# SCH_Task7_3D_PCB_Design_2022-05-29.net
KiCad netlist of a schematic drawn in EasyEDA
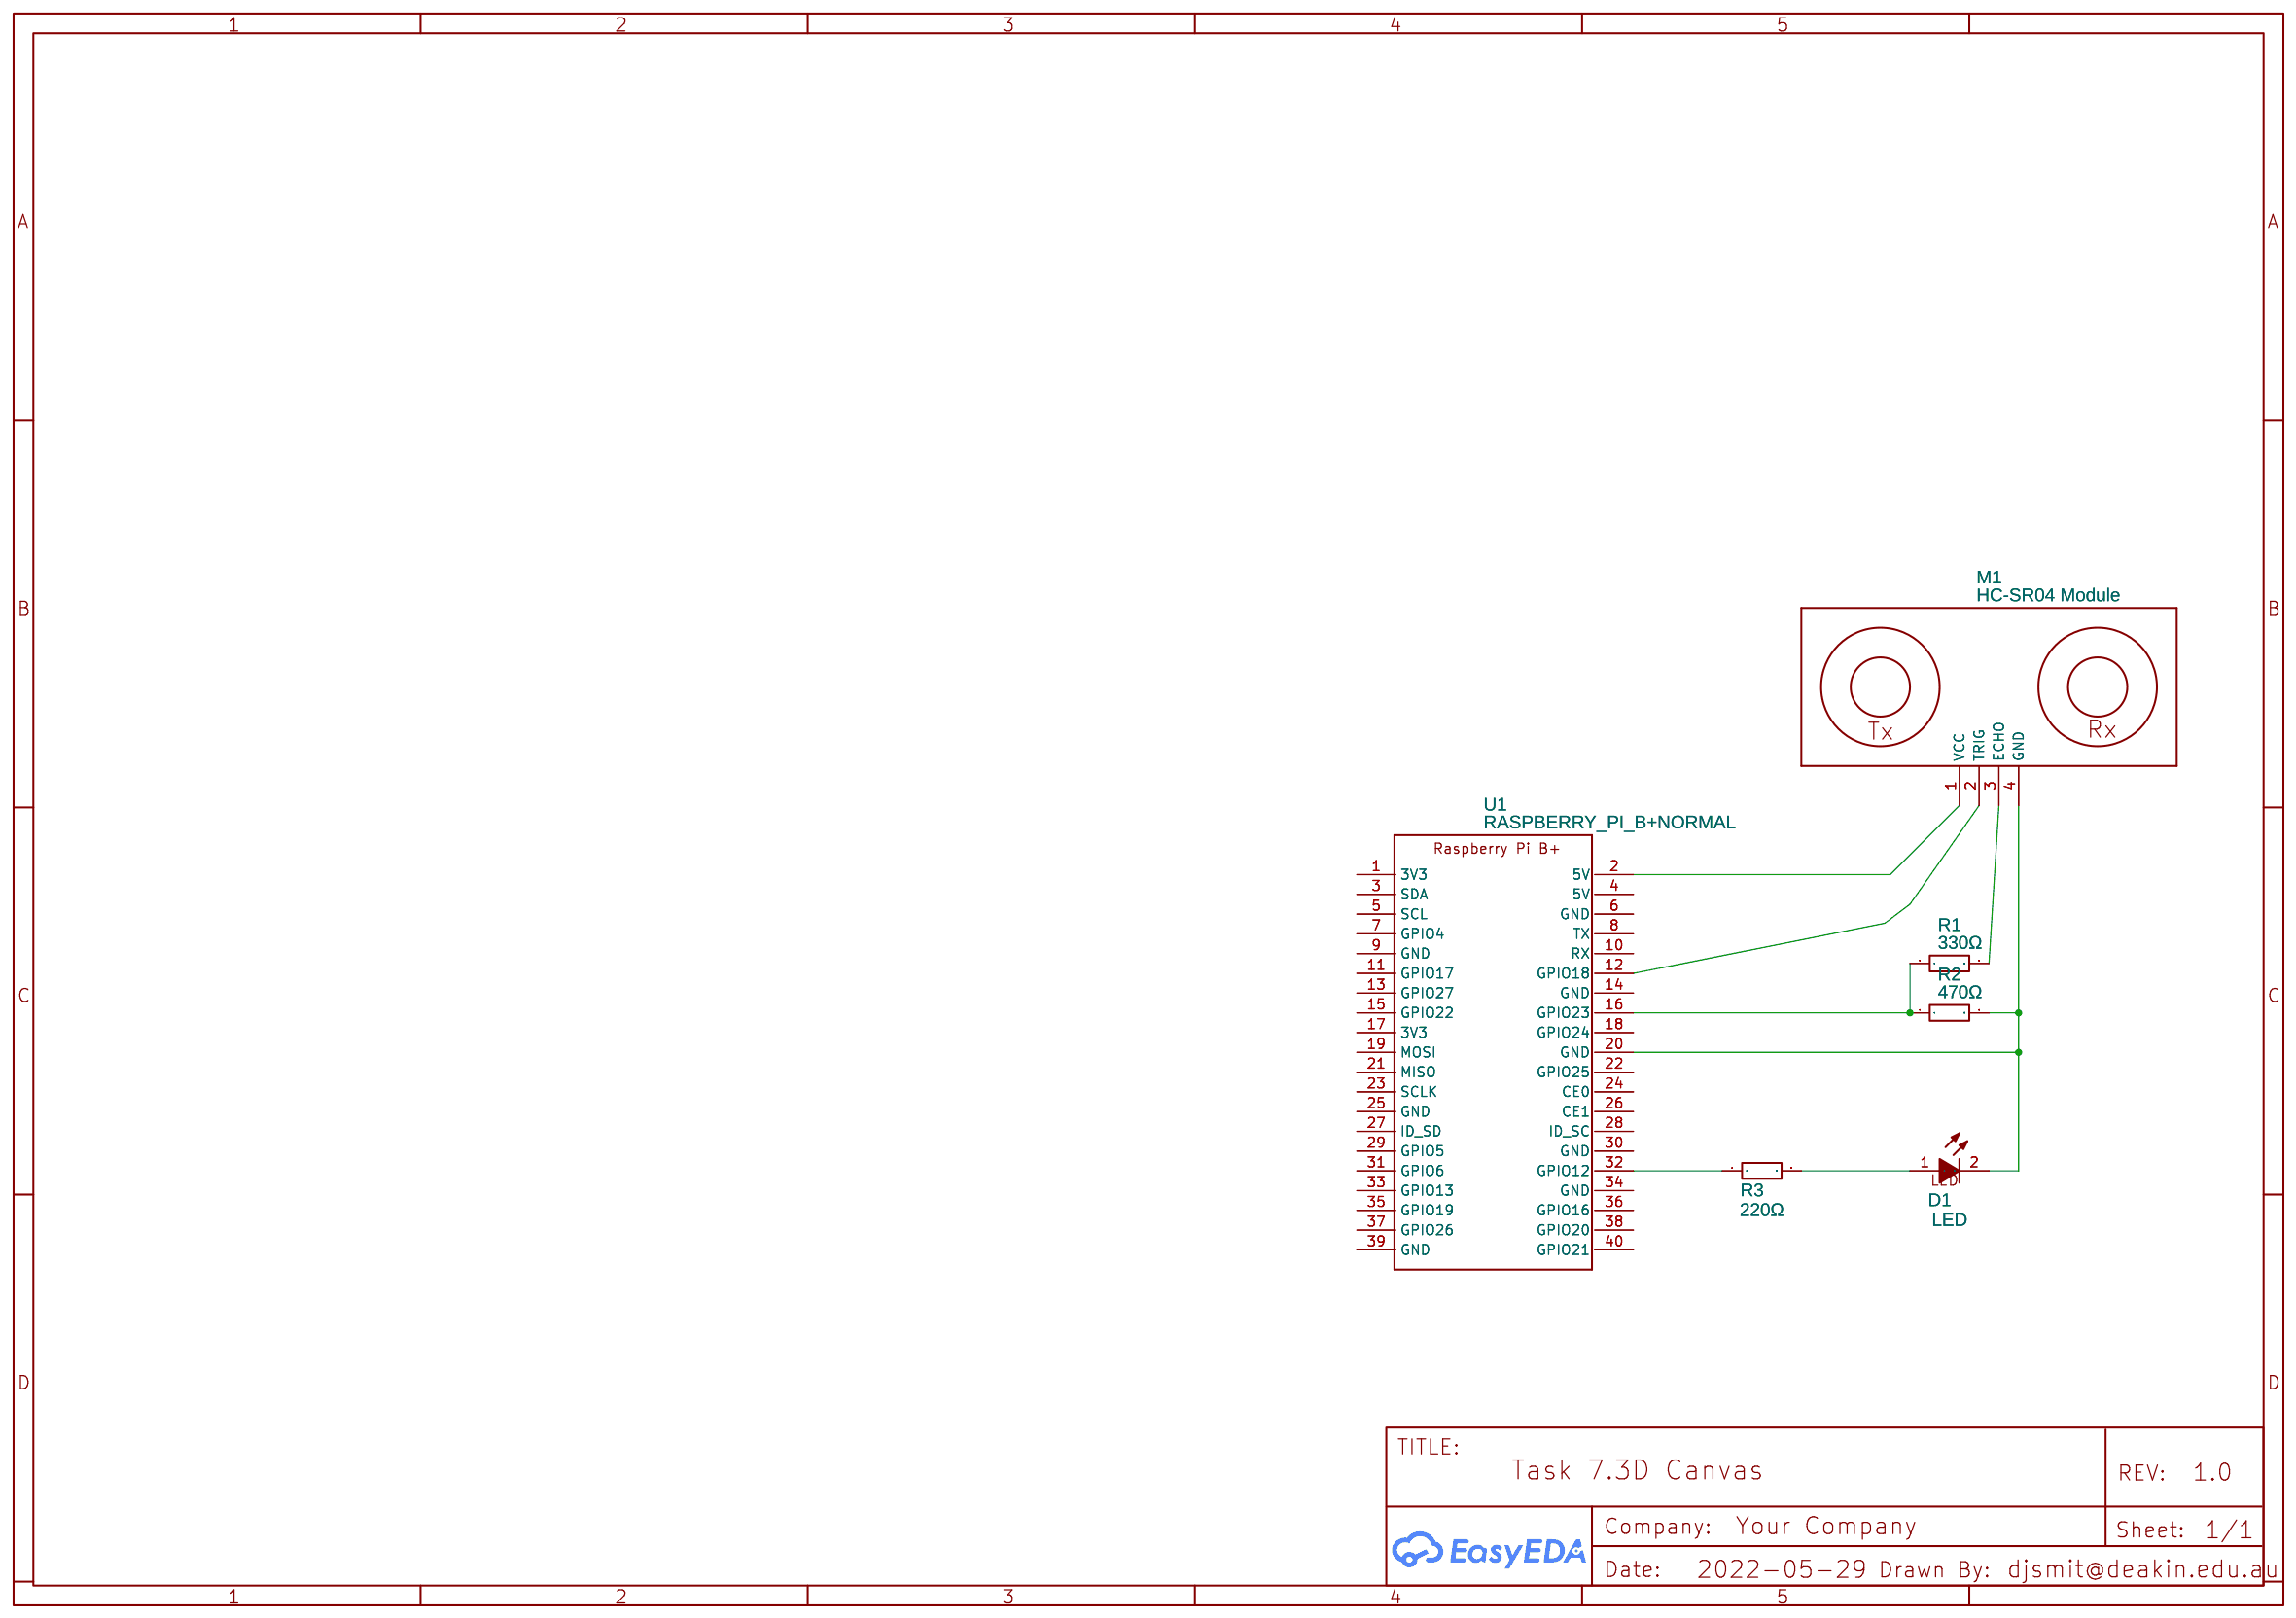
[diagram p0: schematic sheet]

(export (version "E")
  (design (tool "Eeschema 10.0.6"))
  (components
    (comp (ref "D1")
      (value "LED")
      (fields (field (name "BOM_Manufacturer Part") "5600") (field (name "BOM_Supplier Part") "L20325-ND"))
      (libsource (lib "") (part "LED"))
    )
    (comp (ref "M1") (value "HC-SR04 Module") (libsource (lib "") (part "HC-SR04 Module")))
    (comp (ref "R1")
      (value "330Ω")
      (fields
        (field (name "BOM_Manufacturer Part") "MFR0W4F3300A50")
        (field (name "BOM_Supplier Part") "C58608")
      )
      (libsource (lib "") (part "330 OHM Resistor THT (c58608)"))
    )
    (comp (ref "R2")
      (value "470Ω")
      (fields
        (field (name "BOM_Manufacturer Part") "MFR0W4F3300A50")
        (field (name "BOM_Supplier Part") "C58608")
      )
      (libsource (lib "") (part "330 OHM Resistor THT (c58608)"))
    )
    (comp (ref "R3")
      (value "220Ω")
      (fields
        (field (name "BOM_Manufacturer Part") "MFR0W4F3300A50")
        (field (name "BOM_Supplier Part") "C58608")
      )
      (libsource (lib "") (part "330 OHM Resistor THT (c58608)"))
    )
    (comp (ref "U1") (value "RASPBERRY_PI_B+NORMAL") (libsource (lib "") (part "RASPBERRY_PI_B+NORMAL")))
  )
  (nets
    (net (code "1") (name "Net-(D1-A)") (class "Default")
      (node (ref "D1") (pin "1") (pinfunction "A_1") (pintype "input"))
      (node (ref "R3") (pin "2") (pinfunction "2_2") (pintype "input"))
    )
    (net (code "2") (name "Net-(D1-K)") (class "Default")
      (node (ref "D1") (pin "2") (pinfunction "K_2") (pintype "input"))
      (node (ref "M1") (pin "4") (pinfunction "GND_4") (pintype "passive"))
      (node (ref "R2") (pin "2") (pinfunction "2_2") (pintype "input"))
      (node (ref "U1") (pin "20") (pinfunction "GND_20") (pintype "bidirectional"))
    )
    (net (code "3") (name "Net-(M1-ECHO)") (class "Default")
      (node (ref "M1") (pin "3") (pinfunction "ECHO_3") (pintype "output"))
      (node (ref "R1") (pin "2") (pinfunction "2_2") (pintype "input"))
    )
    (net (code "4") (name "Net-(M1-TRIG)") (class "Default")
      (node (ref "M1") (pin "2") (pinfunction "TRIG_2") (pintype "input"))
      (node (ref "U1") (pin "12") (pinfunction "GPIO18_12") (pintype "bidirectional"))
    )
    (net (code "5") (name "Net-(M1-VCC)") (class "Default")
      (node (ref "M1") (pin "1") (pinfunction "VCC_1") (pintype "passive"))
      (node (ref "U1") (pin "2") (pinfunction "5V_2") (pintype "bidirectional"))
    )
    (net (code "6") (name "Net-(U1-GPIO12)") (class "Default")
      (node (ref "R3") (pin "1") (pinfunction "1_1") (pintype "input"))
      (node (ref "U1") (pin "32") (pinfunction "GPIO12_32") (pintype "bidirectional"))
    )
    (net (code "7") (name "Net-(U1-GPIO23)") (class "Default")
      (node (ref "R1") (pin "1") (pinfunction "1_1") (pintype "input"))
      (node (ref "R2") (pin "1") (pinfunction "1_1") (pintype "input"))
      (node (ref "U1") (pin "16") (pinfunction "GPIO23_16") (pintype "bidirectional"))
    )
    (net (code "8") (name "unconnected-(U1-3V3-Pad1)") (class "Default")
      (node (ref "U1") (pin "1") (pinfunction "3V3_1") (pintype "bidirectional"))
    )
    (net (code "9") (name "unconnected-(U1-3V3-Pad17)") (class "Default")
      (node (ref "U1") (pin "17") (pinfunction "3V3_17") (pintype "bidirectional"))
    )
    (net (code "10") (name "unconnected-(U1-5V-Pad4)") (class "Default")
      (node (ref "U1") (pin "4") (pinfunction "5V_4") (pintype "bidirectional"))
    )
    (net (code "11") (name "unconnected-(U1-CE0-Pad24)") (class "Default")
      (node (ref "U1") (pin "24") (pinfunction "CE0_24") (pintype "bidirectional"))
    )
    (net (code "12") (name "unconnected-(U1-CE1-Pad26)") (class "Default")
      (node (ref "U1") (pin "26") (pinfunction "CE1_26") (pintype "bidirectional"))
    )
    (net (code "13") (name "unconnected-(U1-GND-Pad6)") (class "Default")
      (node (ref "U1") (pin "6") (pinfunction "GND_6") (pintype "bidirectional"))
    )
    (net (code "14") (name "unconnected-(U1-GND-Pad9)") (class "Default")
      (node (ref "U1") (pin "9") (pinfunction "GND_9") (pintype "bidirectional"))
    )
    (net (code "15") (name "unconnected-(U1-GND-Pad14)") (class "Default")
      (node (ref "U1") (pin "14") (pinfunction "GND_14") (pintype "bidirectional"))
    )
    (net (code "16") (name "unconnected-(U1-GND-Pad25)") (class "Default")
      (node (ref "U1") (pin "25") (pinfunction "GND_25") (pintype "bidirectional"))
    )
    (net (code "17") (name "unconnected-(U1-GND-Pad30)") (class "Default")
      (node (ref "U1") (pin "30") (pinfunction "GND_30") (pintype "bidirectional"))
    )
    (net (code "18") (name "unconnected-(U1-GND-Pad34)") (class "Default")
      (node (ref "U1") (pin "34") (pinfunction "GND_34") (pintype "bidirectional"))
    )
    (net (code "19") (name "unconnected-(U1-GND-Pad39)") (class "Default")
      (node (ref "U1") (pin "39") (pinfunction "GND_39") (pintype "bidirectional"))
    )
    (net (code "20") (name "unconnected-(U1-GPIO4-Pad7)") (class "Default")
      (node (ref "U1") (pin "7") (pinfunction "GPIO4_7") (pintype "bidirectional"))
    )
    (net (code "21") (name "unconnected-(U1-GPIO5-Pad29)") (class "Default")
      (node (ref "U1") (pin "29") (pinfunction "GPIO5_29") (pintype "bidirectional"))
    )
    (net (code "22") (name "unconnected-(U1-GPIO6-Pad31)") (class "Default")
      (node (ref "U1") (pin "31") (pinfunction "GPIO6_31") (pintype "bidirectional"))
    )
    (net (code "23") (name "unconnected-(U1-GPIO13-Pad33)") (class "Default")
      (node (ref "U1") (pin "33") (pinfunction "GPIO13_33") (pintype "bidirectional"))
    )
    (net (code "24") (name "unconnected-(U1-GPIO16-Pad36)") (class "Default")
      (node (ref "U1") (pin "36") (pinfunction "GPIO16_36") (pintype "bidirectional"))
    )
    (net (code "25") (name "unconnected-(U1-GPIO17-Pad11)") (class "Default")
      (node (ref "U1") (pin "11") (pinfunction "GPIO17_11") (pintype "bidirectional"))
    )
    (net (code "26") (name "unconnected-(U1-GPIO19-Pad35)") (class "Default")
      (node (ref "U1") (pin "35") (pinfunction "GPIO19_35") (pintype "bidirectional"))
    )
    (net (code "27") (name "unconnected-(U1-GPIO20-Pad38)") (class "Default")
      (node (ref "U1") (pin "38") (pinfunction "GPIO20_38") (pintype "bidirectional"))
    )
    (net (code "28") (name "unconnected-(U1-GPIO21-Pad40)") (class "Default")
      (node (ref "U1") (pin "40") (pinfunction "GPIO21_40") (pintype "bidirectional"))
    )
    (net (code "29") (name "unconnected-(U1-GPIO22-Pad15)") (class "Default")
      (node (ref "U1") (pin "15") (pinfunction "GPIO22_15") (pintype "bidirectional"))
    )
    (net (code "30") (name "unconnected-(U1-GPIO24-Pad18)") (class "Default")
      (node (ref "U1") (pin "18") (pinfunction "GPIO24_18") (pintype "bidirectional"))
    )
    (net (code "31") (name "unconnected-(U1-GPIO25-Pad22)") (class "Default")
      (node (ref "U1") (pin "22") (pinfunction "GPIO25_22") (pintype "bidirectional"))
    )
    (net (code "32") (name "unconnected-(U1-GPIO26-Pad37)") (class "Default")
      (node (ref "U1") (pin "37") (pinfunction "GPIO26_37") (pintype "bidirectional"))
    )
    (net (code "33") (name "unconnected-(U1-GPIO27-Pad13)") (class "Default")
      (node (ref "U1") (pin "13") (pinfunction "GPIO27_13") (pintype "bidirectional"))
    )
    (net (code "34") (name "unconnected-(U1-ID_SC-Pad28)") (class "Default")
      (node (ref "U1") (pin "28") (pinfunction "ID_SC_28") (pintype "bidirectional"))
    )
    (net (code "35") (name "unconnected-(U1-ID_SD-Pad27)") (class "Default")
      (node (ref "U1") (pin "27") (pinfunction "ID_SD_27") (pintype "bidirectional"))
    )
    (net (code "36") (name "unconnected-(U1-MISO-Pad21)") (class "Default")
      (node (ref "U1") (pin "21") (pinfunction "MISO_21") (pintype "bidirectional"))
    )
    (net (code "37") (name "unconnected-(U1-MOSI-Pad19)") (class "Default")
      (node (ref "U1") (pin "19") (pinfunction "MOSI_19") (pintype "bidirectional"))
    )
    (net (code "38") (name "unconnected-(U1-RX-Pad10)") (class "Default")
      (node (ref "U1") (pin "10") (pinfunction "RX_10") (pintype "bidirectional"))
    )
    (net (code "39") (name "unconnected-(U1-SCL-Pad5)") (class "Default")
      (node (ref "U1") (pin "5") (pinfunction "SCL_5") (pintype "bidirectional"))
    )
    (net (code "40") (name "unconnected-(U1-SCLK-Pad23)") (class "Default")
      (node (ref "U1") (pin "23") (pinfunction "SCLK_23") (pintype "bidirectional"))
    )
    (net (code "41") (name "unconnected-(U1-SDA-Pad3)") (class "Default")
      (node (ref "U1") (pin "3") (pinfunction "SDA_3") (pintype "bidirectional"))
    )
    (net (code "42") (name "unconnected-(U1-TX-Pad8)") (class "Default")
      (node (ref "U1") (pin "8") (pinfunction "TX_8") (pintype "bidirectional"))
    )
  )
)
